# 04-USB2_Hub_BoardControlPeripherals.net
KiCad netlist of a schematic drawn in Altium Designer
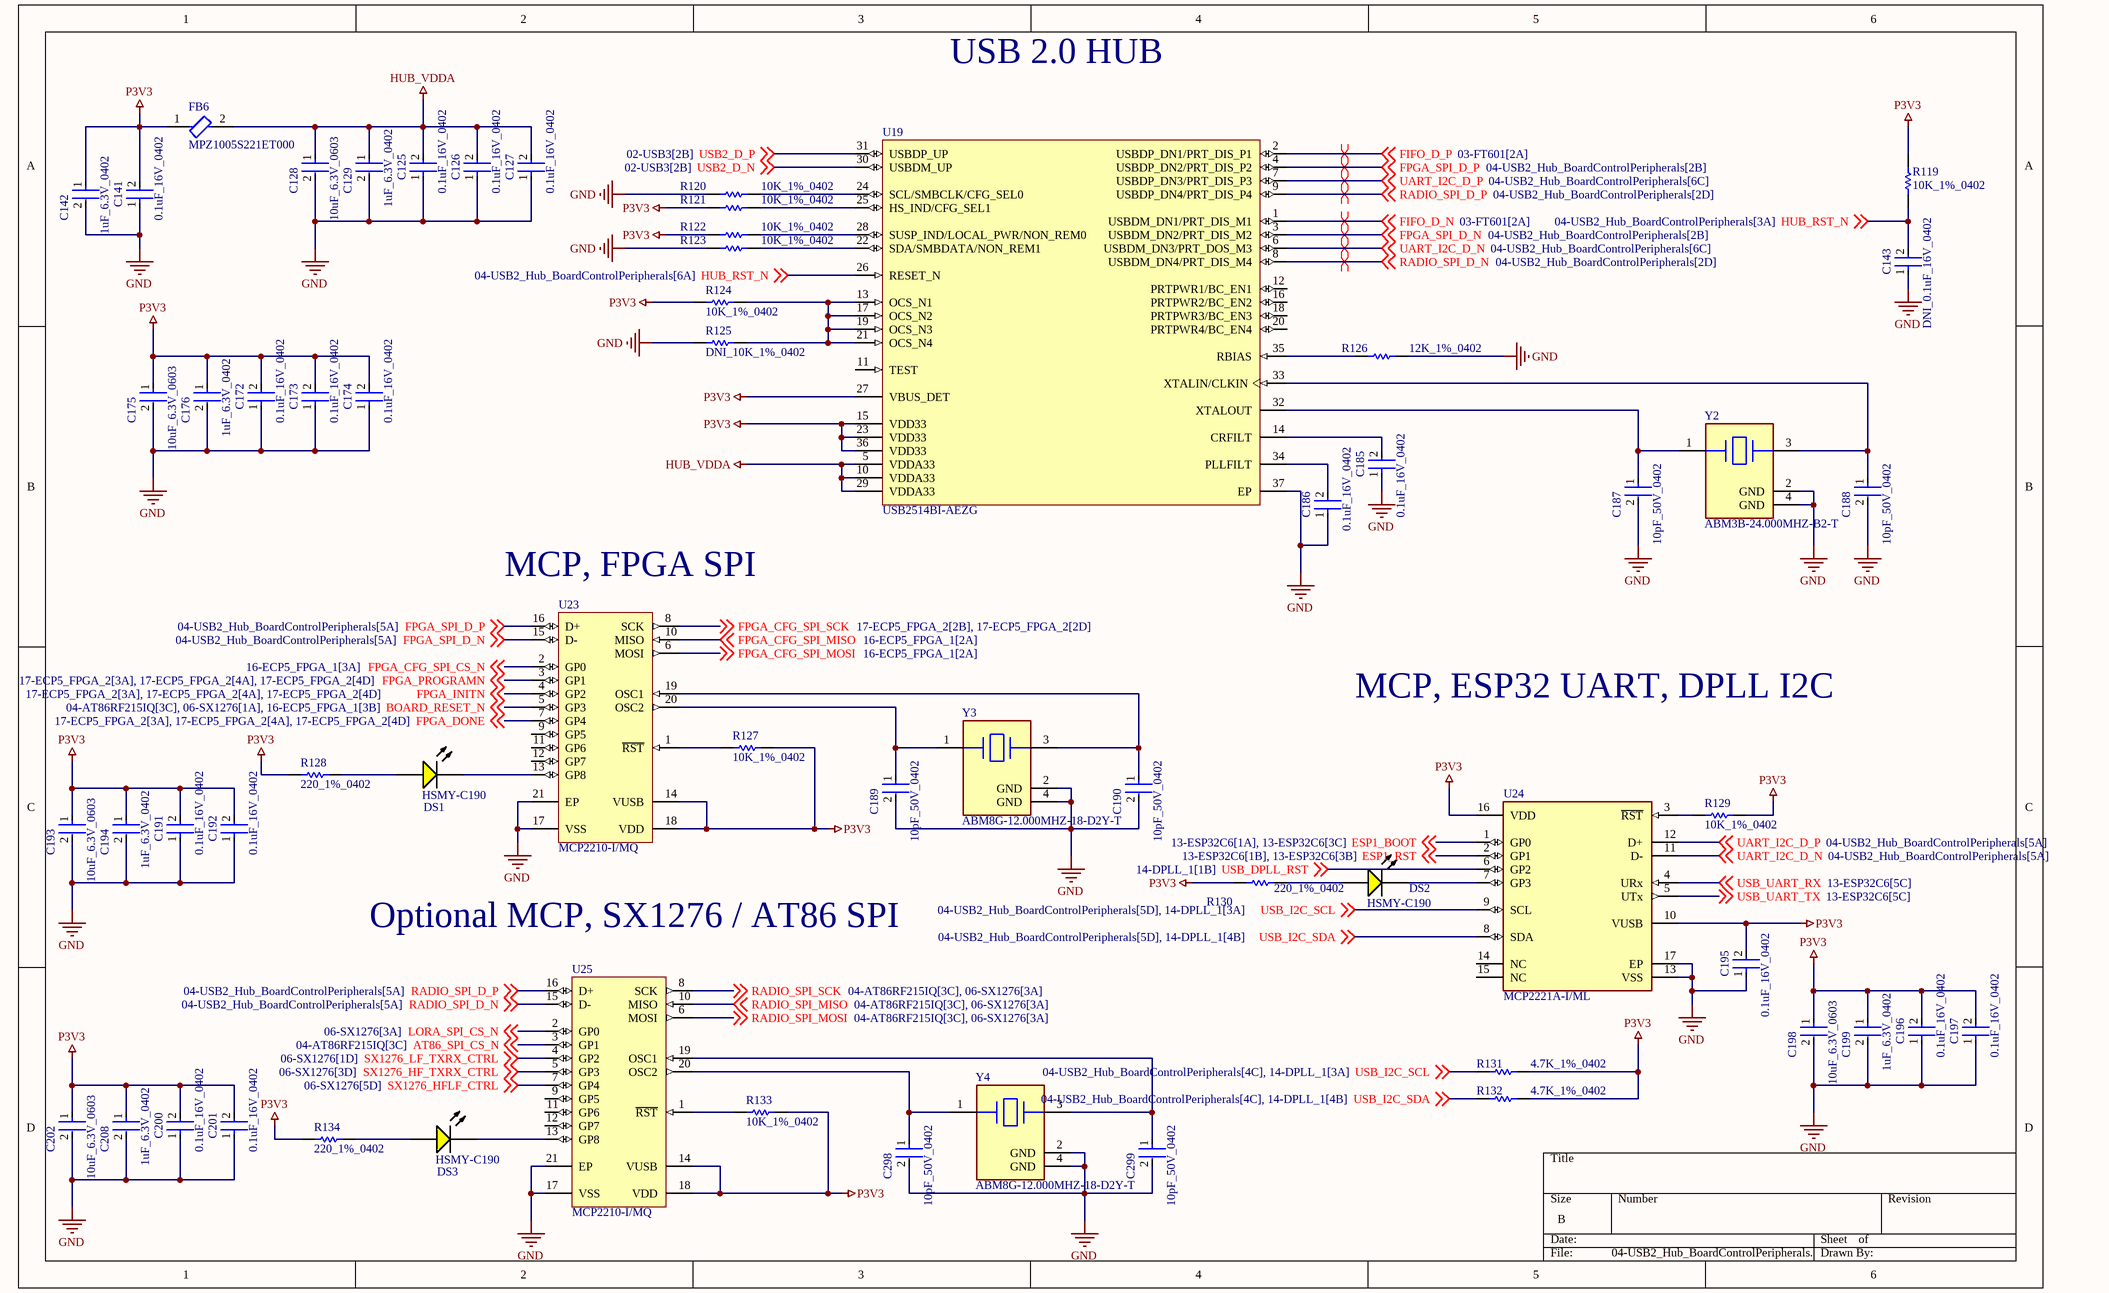
[diagram p0: 04-USB2_Hub_BoardControlPeripherals.SchDoc]

(export (version "E")
  (design (tool "Eeschema 10.0.6"))
  (components
    (comp (ref "C125")
      (value "0.1uF_16V_0402")
      (footprint "FP-C0402-BB-MFG")
      (description "CAP CER 0.1UF 16V 5% X7R 0402")
      (fields
        (field (name "MANUFACTURER") "Kemet")
        (field (name "MANUFACTURER PART NUMBER") "C0402C104J4RACTU")
      )
      (libsource (lib "Altium Content Vault") (part "b4654b650e69147ec39a6b967a45e02"))
    )
    (comp (ref "C126")
      (value "0.1uF_16V_0402")
      (footprint "FP-C0402-BB-MFG")
      (description "CAP CER 0.1UF 16V 5% X7R 0402")
      (fields
        (field (name "MANUFACTURER") "Kemet")
        (field (name "MANUFACTURER PART NUMBER") "C0402C104J4RACTU")
      )
      (libsource (lib "Altium Content Vault") (part "b4654b650e69147ec39a6b967a45e02"))
    )
    (comp (ref "C127")
      (value "0.1uF_16V_0402")
      (footprint "FP-C0402-BB-MFG")
      (description "CAP CER 0.1UF 16V 5% X7R 0402")
      (fields
        (field (name "MANUFACTURER") "Kemet")
        (field (name "MANUFACTURER PART NUMBER") "C0402C104J4RACTU")
      )
      (libsource (lib "Altium Content Vault") (part "b4654b650e69147ec39a6b967a45e02"))
    )
    (comp (ref "C128")
      (value "10uF_6.3V_0603")
      (footprint "FP-GRM188-0_1-e0_2_0_55-IPC_A")
      (description "Chip Multilayer Ceramic Capacitors for General Purpose, 0603, 10uF, X5R, 15%, 20%, 6.3V")
      (fields (field (name "VOLTAGE") "6.3V") (field (name "TOLERANCE") "20%"))
      (libsource (lib "Altium Content Vault") (part "02cd4be3c70576c341d710602a673aa"))
    )
    (comp (ref "C129")
      (value "1uF_6.3V_0402")
      (footprint "FP-CC0402-MFG")
      (description "CAP CER 1UF 6.3V X5R 0402")
      (fields
        (field (name "MANUFACTURER") "YAGEO")
        (field (name "OCTOPART") "https://octopart.com/cc0402krx5r5bb105-yageo-42244618")
      )
      (libsource (lib "Altium Content Vault") (part "11868f565c42a9108669ba33697ecf6"))
    )
    (comp (ref "C141")
      (value "0.1uF_16V_0402")
      (footprint "FP-C0402-BB-MFG")
      (description "CAP CER 0.1UF 16V 5% X7R 0402")
      (fields
        (field (name "MANUFACTURER") "Kemet")
        (field (name "MANUFACTURER PART NUMBER") "C0402C104J4RACTU")
      )
      (libsource (lib "Altium Content Vault") (part "b4654b650e69147ec39a6b967a45e02"))
    )
    (comp (ref "C142")
      (value "1uF_6.3V_0402")
      (footprint "FP-CC0402-MFG")
      (description "CAP CER 1UF 6.3V X5R 0402")
      (fields
        (field (name "MANUFACTURER") "YAGEO")
        (field (name "OCTOPART") "https://octopart.com/cc0402krx5r5bb105-yageo-42244618")
      )
      (libsource (lib "Altium Content Vault") (part "11868f565c42a9108669ba33697ecf6"))
    )
    (comp (ref "C143")
      (value "DNI_0.1uF_16V_0402")
      (footprint "FP-C0402-BB-MFG")
      (description "CAP CER 0.1UF 16V 5% X7R 0402")
      (fields
        (field (name "MANUFACTURER") "Kemet")
        (field (name "MANUFACTURER PART NUMBER") "C0402C104J4RACTU")
      )
      (libsource (lib "Altium Content Vault") (part "b4654b650e69147ec39a6b967a45e02"))
    )
    (comp (ref "C172")
      (value "0.1uF_16V_0402")
      (footprint "FP-C0402-BB-MFG")
      (description "CAP CER 0.1UF 16V 5% X7R 0402")
      (fields
        (field (name "MANUFACTURER") "Kemet")
        (field (name "MANUFACTURER PART NUMBER") "C0402C104J4RACTU")
      )
      (libsource (lib "Altium Content Vault") (part "b4654b650e69147ec39a6b967a45e02"))
    )
    (comp (ref "C173")
      (value "0.1uF_16V_0402")
      (footprint "FP-C0402-BB-MFG")
      (description "CAP CER 0.1UF 16V 5% X7R 0402")
      (fields
        (field (name "MANUFACTURER") "Kemet")
        (field (name "MANUFACTURER PART NUMBER") "C0402C104J4RACTU")
      )
      (libsource (lib "Altium Content Vault") (part "b4654b650e69147ec39a6b967a45e02"))
    )
    (comp (ref "C174")
      (value "0.1uF_16V_0402")
      (footprint "FP-C0402-BB-MFG")
      (description "CAP CER 0.1UF 16V 5% X7R 0402")
      (fields
        (field (name "MANUFACTURER") "Kemet")
        (field (name "MANUFACTURER PART NUMBER") "C0402C104J4RACTU")
      )
      (libsource (lib "Altium Content Vault") (part "b4654b650e69147ec39a6b967a45e02"))
    )
    (comp (ref "C175")
      (value "10uF_6.3V_0603")
      (footprint "FP-GRM188-0_1-e0_2_0_55-IPC_A")
      (description "Chip Multilayer Ceramic Capacitors for General Purpose, 0603, 10uF, X5R, 15%, 20%, 6.3V")
      (fields (field (name "VOLTAGE") "6.3V") (field (name "TOLERANCE") "20%"))
      (libsource (lib "Altium Content Vault") (part "02cd4be3c70576c341d710602a673aa"))
    )
    (comp (ref "C176")
      (value "1uF_6.3V_0402")
      (footprint "FP-CC0402-MFG")
      (description "CAP CER 1UF 6.3V X5R 0402")
      (fields
        (field (name "MANUFACTURER") "YAGEO")
        (field (name "OCTOPART") "https://octopart.com/cc0402krx5r5bb105-yageo-42244618")
      )
      (libsource (lib "Altium Content Vault") (part "11868f565c42a9108669ba33697ecf6"))
    )
    (comp (ref "C185")
      (value "0.1uF_16V_0402")
      (footprint "FP-C0402-BB-MFG")
      (description "CAP CER 0.1UF 16V 5% X7R 0402")
      (fields
        (field (name "MANUFACTURER") "Kemet")
        (field (name "MANUFACTURER PART NUMBER") "C0402C104J4RACTU")
      )
      (libsource (lib "Altium Content Vault") (part "b4654b650e69147ec39a6b967a45e02"))
    )
    (comp (ref "C186")
      (value "0.1uF_16V_0402")
      (footprint "FP-C0402-BB-MFG")
      (description "CAP CER 0.1UF 16V 5% X7R 0402")
      (fields
        (field (name "MANUFACTURER") "Kemet")
        (field (name "MANUFACTURER PART NUMBER") "C0402C104J4RACTU")
      )
      (libsource (lib "Altium Content Vault") (part "b4654b650e69147ec39a6b967a45e02"))
    )
    (comp (ref "C187")
      (value "10pF_50V_0402")
      (footprint "FP-C0402-BB-MFG")
      (fields
        (field (name "MANUFACTURER PART NUMBER") "C0402C100J5GACTU")
        (field (name "MANUFACTURER") "Kemet")
        (field (name "OCTOPART") "https://octopart.com/c0402c100j5gactu-kemet-108448")
      )
      (libsource (lib "Altium Content Vault") (part "b4654b650e69147ec39a6b967a45e02"))
    )
    (comp (ref "C188")
      (value "10pF_50V_0402")
      (footprint "FP-C0402-BB-MFG")
      (fields
        (field (name "MANUFACTURER PART NUMBER") "C0402C100J5GACTU")
        (field (name "MANUFACTURER") "Kemet")
        (field (name "OCTOPART") "https://octopart.com/c0402c100j5gactu-kemet-108448")
      )
      (libsource (lib "Altium Content Vault") (part "b4654b650e69147ec39a6b967a45e02"))
    )
    (comp (ref "C189")
      (value "10pF_50V_0402")
      (footprint "FP-C0402-BB-MFG")
      (fields
        (field (name "MANUFACTURER PART NUMBER") "C0402C100J5GACTU")
        (field (name "MANUFACTURER") "Kemet")
        (field (name "OCTOPART") "https://octopart.com/c0402c100j5gactu-kemet-108448")
      )
      (libsource (lib "Altium Content Vault") (part "b4654b650e69147ec39a6b967a45e02"))
    )
    (comp (ref "C190")
      (value "10pF_50V_0402")
      (footprint "FP-C0402-BB-MFG")
      (fields
        (field (name "MANUFACTURER PART NUMBER") "C0402C100J5GACTU")
        (field (name "MANUFACTURER") "Kemet")
        (field (name "OCTOPART") "https://octopart.com/c0402c100j5gactu-kemet-108448")
      )
      (libsource (lib "Altium Content Vault") (part "b4654b650e69147ec39a6b967a45e02"))
    )
    (comp (ref "C191")
      (value "0.1uF_16V_0402")
      (footprint "FP-C0402-BB-MFG")
      (description "CAP CER 0.1UF 16V 5% X7R 0402")
      (fields
        (field (name "MANUFACTURER") "Kemet")
        (field (name "MANUFACTURER PART NUMBER") "C0402C104J4RACTU")
      )
      (libsource (lib "Altium Content Vault") (part "b4654b650e69147ec39a6b967a45e02"))
    )
    (comp (ref "C192")
      (value "0.1uF_16V_0402")
      (footprint "FP-C0402-BB-MFG")
      (description "CAP CER 0.1UF 16V 5% X7R 0402")
      (fields
        (field (name "MANUFACTURER") "Kemet")
        (field (name "MANUFACTURER PART NUMBER") "C0402C104J4RACTU")
      )
      (libsource (lib "Altium Content Vault") (part "b4654b650e69147ec39a6b967a45e02"))
    )
    (comp (ref "C193")
      (value "10uF_6.3V_0603")
      (footprint "FP-GRM188-0_1-e0_2_0_55-IPC_A")
      (description "Chip Multilayer Ceramic Capacitors for General Purpose, 0603, 10uF, X5R, 15%, 20%, 6.3V")
      (fields (field (name "VOLTAGE") "6.3V") (field (name "TOLERANCE") "20%"))
      (libsource (lib "Altium Content Vault") (part "02cd4be3c70576c341d710602a673aa"))
    )
    (comp (ref "C194")
      (value "1uF_6.3V_0402")
      (footprint "FP-CC0402-MFG")
      (description "CAP CER 1UF 6.3V X5R 0402")
      (fields
        (field (name "MANUFACTURER") "YAGEO")
        (field (name "OCTOPART") "https://octopart.com/cc0402krx5r5bb105-yageo-42244618")
      )
      (libsource (lib "Altium Content Vault") (part "11868f565c42a9108669ba33697ecf6"))
    )
    (comp (ref "C195")
      (value "0.1uF_16V_0402")
      (footprint "FP-C0402-BB-MFG")
      (description "CAP CER 0.1UF 16V 5% X7R 0402")
      (fields
        (field (name "MANUFACTURER") "Kemet")
        (field (name "MANUFACTURER PART NUMBER") "C0402C104J4RACTU")
      )
      (libsource (lib "Altium Content Vault") (part "b4654b650e69147ec39a6b967a45e02"))
    )
    (comp (ref "C196")
      (value "0.1uF_16V_0402")
      (footprint "FP-C0402-BB-MFG")
      (description "CAP CER 0.1UF 16V 5% X7R 0402")
      (fields
        (field (name "MANUFACTURER") "Kemet")
        (field (name "MANUFACTURER PART NUMBER") "C0402C104J4RACTU")
      )
      (libsource (lib "Altium Content Vault") (part "b4654b650e69147ec39a6b967a45e02"))
    )
    (comp (ref "C197")
      (value "0.1uF_16V_0402")
      (footprint "FP-C0402-BB-MFG")
      (description "CAP CER 0.1UF 16V 5% X7R 0402")
      (fields
        (field (name "MANUFACTURER") "Kemet")
        (field (name "MANUFACTURER PART NUMBER") "C0402C104J4RACTU")
      )
      (libsource (lib "Altium Content Vault") (part "b4654b650e69147ec39a6b967a45e02"))
    )
    (comp (ref "C198")
      (value "10uF_6.3V_0603")
      (footprint "FP-GRM188-0_1-e0_2_0_55-IPC_A")
      (description "Chip Multilayer Ceramic Capacitors for General Purpose, 0603, 10uF, X5R, 15%, 20%, 6.3V")
      (fields (field (name "VOLTAGE") "6.3V") (field (name "TOLERANCE") "20%"))
      (libsource (lib "Altium Content Vault") (part "02cd4be3c70576c341d710602a673aa"))
    )
    (comp (ref "C199")
      (value "1uF_6.3V_0402")
      (footprint "FP-CC0402-MFG")
      (description "CAP CER 1UF 6.3V X5R 0402")
      (fields
        (field (name "MANUFACTURER") "YAGEO")
        (field (name "OCTOPART") "https://octopart.com/cc0402krx5r5bb105-yageo-42244618")
      )
      (libsource (lib "Altium Content Vault") (part "11868f565c42a9108669ba33697ecf6"))
    )
    (comp (ref "C200")
      (value "0.1uF_16V_0402")
      (footprint "FP-C0402-BB-MFG")
      (description "CAP CER 0.1UF 16V 5% X7R 0402")
      (fields
        (field (name "MANUFACTURER") "Kemet")
        (field (name "MANUFACTURER PART NUMBER") "C0402C104J4RACTU")
      )
      (libsource (lib "Altium Content Vault") (part "b4654b650e69147ec39a6b967a45e02"))
    )
    (comp (ref "C201")
      (value "0.1uF_16V_0402")
      (footprint "FP-C0402-BB-MFG")
      (description "CAP CER 0.1UF 16V 5% X7R 0402")
      (fields
        (field (name "MANUFACTURER") "Kemet")
        (field (name "MANUFACTURER PART NUMBER") "C0402C104J4RACTU")
      )
      (libsource (lib "Altium Content Vault") (part "b4654b650e69147ec39a6b967a45e02"))
    )
    (comp (ref "C202")
      (value "10uF_6.3V_0603")
      (footprint "FP-GRM188-0_1-e0_2_0_55-IPC_A")
      (description "Chip Multilayer Ceramic Capacitors for General Purpose, 0603, 10uF, X5R, 15%, 20%, 6.3V")
      (fields (field (name "VOLTAGE") "6.3V") (field (name "TOLERANCE") "20%"))
      (libsource (lib "Altium Content Vault") (part "02cd4be3c70576c341d710602a673aa"))
    )
    (comp (ref "C208")
      (value "1uF_6.3V_0402")
      (footprint "FP-CC0402-MFG")
      (description "CAP CER 1UF 6.3V X5R 0402")
      (fields
        (field (name "MANUFACTURER") "YAGEO")
        (field (name "OCTOPART") "https://octopart.com/cc0402krx5r5bb105-yageo-42244618")
      )
      (libsource (lib "Altium Content Vault") (part "11868f565c42a9108669ba33697ecf6"))
    )
    (comp (ref "C298")
      (value "10pF_50V_0402")
      (footprint "FP-C0402-BB-MFG")
      (fields
        (field (name "MANUFACTURER PART NUMBER") "C0402C100J5GACTU")
        (field (name "MANUFACTURER") "Kemet")
        (field (name "OCTOPART") "https://octopart.com/c0402c100j5gactu-kemet-108448")
      )
      (libsource (lib "Altium Content Vault") (part "b4654b650e69147ec39a6b967a45e02"))
    )
    (comp (ref "C299")
      (value "10pF_50V_0402")
      (footprint "FP-C0402-BB-MFG")
      (fields
        (field (name "MANUFACTURER PART NUMBER") "C0402C100J5GACTU")
        (field (name "MANUFACTURER") "Kemet")
        (field (name "OCTOPART") "https://octopart.com/c0402c100j5gactu-kemet-108448")
      )
      (libsource (lib "Altium Content Vault") (part "b4654b650e69147ec39a6b967a45e02"))
    )
    (comp (ref "DS1")
      (value "HSMY-C190")
      (footprint "AVAG-HSMX-C190_V")
      (description "LED Uni-Color Yellow, 65 mW, 20 mA, -40 to 85 degC, 2-Pin SMD, RoHS, Tape and Reel")
      (fields (field (name "TOLERANCE") "1%"))
      (libsource (lib "Altium Content Vault") (part "LED-YELLOW-AK-2"))
    )
    (comp (ref "DS2")
      (value "HSMY-C190")
      (footprint "AVAG-HSMX-C190_V")
      (description "LED Uni-Color Yellow, 65 mW, 20 mA, -40 to 85 degC, 2-Pin SMD, RoHS, Tape and Reel")
      (fields (field (name "TOLERANCE") "1%"))
      (libsource (lib "Altium Content Vault") (part "LED-YELLOW-AK-2"))
    )
    (comp (ref "DS3")
      (value "HSMY-C190")
      (footprint "AVAG-HSMX-C190_V")
      (description "LED Uni-Color Yellow, 65 mW, 20 mA, -40 to 85 degC, 2-Pin SMD, RoHS, Tape and Reel")
      (fields (field (name "TOLERANCE") "1%"))
      (libsource (lib "Altium Content Vault") (part "LED-YELLOW-AK-2"))
    )
    (comp (ref "FB6")
      (value "MPZ1005S221ET000")
      (footprint "FP-MPZ1005-IPC_A")
      (description "Power line Ferrite Bead 220Ω @ 100MHz 0.9A DCR 0.22Ω SMD 0402")
      (fields (field (name "TOLERANCE") "25%"))
      (libsource (lib "Altium Content Vault") (part "5f30dd21d616792df468990f7003faa"))
    )
    (comp (ref "R119")
      (value "10K_1%_0402")
      (footprint "RESC1005X40X25NL10T10")
      (fields (field (name "MANUFACTURER") "Bourns") (field (name "PART NUMBER") "CR0402-FX-1002GLF"))
      (libsource (lib "Altium Content Vault") (part "RES"))
    )
    (comp (ref "R120")
      (value "10K_1%_0402")
      (footprint "RESC1005X40X25NL10T10")
      (fields (field (name "MANUFACTURER") "Bourns") (field (name "PART NUMBER") "CR0402-FX-1002GLF"))
      (libsource (lib "Altium Content Vault") (part "RES"))
    )
    (comp (ref "R121")
      (value "10K_1%_0402")
      (footprint "RESC1005X40X25NL10T10")
      (fields (field (name "MANUFACTURER") "Bourns") (field (name "PART NUMBER") "CR0402-FX-1002GLF"))
      (libsource (lib "Altium Content Vault") (part "RES"))
    )
    (comp (ref "R122")
      (value "10K_1%_0402")
      (footprint "RESC1005X40X25NL10T10")
      (fields (field (name "MANUFACTURER") "Bourns") (field (name "PART NUMBER") "CR0402-FX-1002GLF"))
      (libsource (lib "Altium Content Vault") (part "RES"))
    )
    (comp (ref "R123")
      (value "10K_1%_0402")
      (footprint "RESC1005X40X25NL10T10")
      (fields (field (name "MANUFACTURER") "Bourns") (field (name "PART NUMBER") "CR0402-FX-1002GLF"))
      (libsource (lib "Altium Content Vault") (part "RES"))
    )
    (comp (ref "R124")
      (value "10K_1%_0402")
      (footprint "RESC1005X40X25NL10T10")
      (fields (field (name "MANUFACTURER") "Bourns") (field (name "PART NUMBER") "CR0402-FX-1002GLF"))
      (libsource (lib "Altium Content Vault") (part "RES"))
    )
    (comp (ref "R125")
      (value "DNI_10K_1%_0402")
      (footprint "RESC1005X40X25NL10T10")
      (fields (field (name "MANUFACTURER") "Bourns") (field (name "PART NUMBER") "CR0402-FX-1002GLF"))
      (libsource (lib "Altium Content Vault") (part "RES"))
    )
    (comp (ref "R126")
      (value "12K_1%_0402")
      (footprint "RESC1005X40X25LL10T10")
      (fields
        (field (name "PART NUMBER") "CRG0402F12K")
        (field (name "MANUFACTURER") "TE Connectivity / AMP")
      )
      (libsource (lib "Altium Content Vault") (part "RES"))
    )
    (comp (ref "R127")
      (value "10K_1%_0402")
      (footprint "RESC1005X40X25NL10T10")
      (fields (field (name "MANUFACTURER") "Bourns") (field (name "PART NUMBER") "CR0402-FX-1002GLF"))
      (libsource (lib "Altium Content Vault") (part "RES"))
    )
    (comp (ref "R128")
      (value "220_1%_0402")
      (footprint "RESC1005X40X25LL05T05")
      (fields (field (name "MANUFACTURER") "Panasonic") (field (name "PART NUMBER") "ERJ2RKF2200X"))
      (libsource (lib "Altium Content Vault") (part "RES"))
    )
    (comp (ref "R129")
      (value "10K_1%_0402")
      (footprint "RESC1005X40X25NL10T10")
      (fields (field (name "MANUFACTURER") "Bourns") (field (name "PART NUMBER") "CR0402-FX-1002GLF"))
      (libsource (lib "Altium Content Vault") (part "RES"))
    )
    (comp (ref "R130")
      (value "220_1%_0402")
      (footprint "RESC1005X40X25LL05T05")
      (fields (field (name "MANUFACTURER") "Panasonic") (field (name "PART NUMBER") "ERJ2RKF2200X"))
      (libsource (lib "Altium Content Vault") (part "RES"))
    )
    (comp (ref "R131")
      (value "4.7K_1%_0402")
      (footprint "RESC1005X40X25NL05T10")
      (fields (field (name "MANUFACTURER") "Yageo / Phycomp") (field (name "PART NUMBER") "RC0402FR-074K7L"))
      (libsource (lib "Altium Content Vault") (part "RES"))
    )
    (comp (ref "R132")
      (value "4.7K_1%_0402")
      (footprint "RESC1005X40X25NL05T10")
      (fields (field (name "MANUFACTURER") "Yageo / Phycomp") (field (name "PART NUMBER") "RC0402FR-074K7L"))
      (libsource (lib "Altium Content Vault") (part "RES"))
    )
    (comp (ref "R133")
      (value "10K_1%_0402")
      (footprint "RESC1005X40X25NL10T10")
      (fields (field (name "MANUFACTURER") "Bourns") (field (name "PART NUMBER") "CR0402-FX-1002GLF"))
      (libsource (lib "Altium Content Vault") (part "RES"))
    )
    (comp (ref "R134")
      (value "220_1%_0402")
      (footprint "RESC1005X40X25LL05T05")
      (fields (field (name "MANUFACTURER") "Panasonic") (field (name "PART NUMBER") "ERJ2RKF2200X"))
      (libsource (lib "Altium Content Vault") (part "RES"))
    )
    (comp (ref "U19")
      (value "USB2514BI-AEZG")
      (footprint "MCHP-QFN-36_V")
      (description "USB 2.0 Hi-Speed Hub Controller, 3 to 3.6 V, -40 to 85 degC, 36-Pin QFN, RoHS, Tape and Reel")
      (fields (field (name "MANUFACTURER") "Microchip"))
      (libsource (lib "Altium Content Vault") (part "MCHP-USB2514-QFN-36"))
    )
    (comp (ref "U23")
      (value "MCP2210-I/MQ")
      (footprint "QFN-MQ20_L")
      (description "USB-to-SPI Protocol Converter with GPIO (Master Mode), 20-Pin QFN, Industrial Temperature")
      (libsource (lib "Altium Content Vault") (part "COM-USB-MCP2210-21"))
    )
    (comp (ref "U24")
      (value "MCP2221A-I/ML")
      (footprint "FP-C04-127-MFG")
      (description "IC USB TO I2C/UART 16QFN")
      (libsource (lib "Altium Content Vault") (part "9a58687fb20c11cd38d39b7dac8df0f"))
    )
    (comp (ref "U25")
      (value "MCP2210-I/MQ")
      (footprint "QFN-MQ20_L")
      (description "USB-to-SPI Protocol Converter with GPIO (Master Mode), 20-Pin QFN, Industrial Temperature")
      (libsource (lib "Altium Content Vault") (part "COM-USB-MCP2210-21"))
    )
    (comp (ref "Y2")
      (value "ABM3B-24.000MHZ-B2-T")
      (footprint "FP-ABM3B-MFG")
      (description "Crystal 24MHz ±20ppm 18pF SMD-4 5mm x 3.2mm")
      (fields (field (name "TOLERANCE") "20ppm"))
      (libsource (lib "Altium Content Vault") (part "48e526d86b7f2615d98721063c72f49"))
    )
    (comp (ref "Y3")
      (value "ABM8G-12.000MHZ-18-D2Y-T")
      (footprint "FP-ABM8G-MFG")
      (description "Crystal 12MHz ±20ppm (Tol) ±30ppm (Stability) 18pF FUND 120Ω 4-Pin SMD T/R")
      (fields (field (name "TOLERANCE") "20ppm"))
      (libsource (lib "Altium Content Vault") (part "48e526d86b7f2615d98721063c72f49"))
    )
    (comp (ref "Y4")
      (value "ABM8G-12.000MHZ-18-D2Y-T")
      (footprint "FP-ABM8G-MFG")
      (description "Crystal 12MHz ±20ppm (Tol) ±30ppm (Stability) 18pF FUND 120Ω 4-Pin SMD T/R")
      (fields (field (name "TOLERANCE") "20ppm"))
      (libsource (lib "Altium Content Vault") (part "48e526d86b7f2615d98721063c72f49"))
    )
  )
  (nets
    (net (code "1") (name "AT86_SPI_CS_N") (class "Default")
      (node (ref "U25") (pin "3") (pinfunction "GP1_3") (pintype "bidirectional"))
    )
    (net (code "2") (name "BOARD_RESET_N") (class "Default")
      (node (ref "U23") (pin "5") (pinfunction "GP3_5") (pintype "bidirectional"))
    )
    (net (code "3") (name "ESP1_BOOT") (class "Default")
      (node (ref "U24") (pin "1") (pinfunction "GP0_1") (pintype "bidirectional"))
    )
    (net (code "4") (name "ESP1_RST") (class "Default")
      (node (ref "U24") (pin "2") (pinfunction "GP1_2") (pintype "bidirectional"))
    )
    (net (code "5") (name "FIFO_D_N") (class "Default")
      (node (ref "U19") (pin "1") (pinfunction "USBDM_DN1/PRT_DIS_M1_1") (pintype "bidirectional"))
    )
    (net (code "6") (name "FIFO_D_P") (class "Default")
      (node (ref "U19") (pin "2") (pinfunction "USBDP_DN1/PRT_DIS_P1_2") (pintype "bidirectional"))
    )
    (net (code "7") (name "FPGA_CFG_SPI_CS_N") (class "Default")
      (node (ref "U23") (pin "2") (pinfunction "GP0_2") (pintype "bidirectional"))
    )
    (net (code "8") (name "FPGA_CFG_SPI_MISO") (class "Default")
      (node (ref "U23") (pin "10") (pinfunction "MISO_10") (pintype "input"))
    )
    (net (code "9") (name "FPGA_CFG_SPI_MOSI") (class "Default")
      (node (ref "U23") (pin "6") (pinfunction "MOSI_6") (pintype "output"))
    )
    (net (code "10") (name "FPGA_CFG_SPI_SCK") (class "Default")
      (node (ref "U23") (pin "8") (pinfunction "SCK_8") (pintype "output"))
    )
    (net (code "11") (name "FPGA_DONE") (class "Default")
      (node (ref "U23") (pin "7") (pinfunction "GP4_7") (pintype "bidirectional"))
    )
    (net (code "12") (name "FPGA_INITN") (class "Default")
      (node (ref "U23") (pin "4") (pinfunction "GP2_4") (pintype "bidirectional"))
    )
    (net (code "13") (name "FPGA_PROGRAMN") (class "Default")
      (node (ref "U23") (pin "3") (pinfunction "GP1_3") (pintype "bidirectional"))
    )
    (net (code "14") (name "FPGA_SPI_D_N") (class "Default")
      (node (ref "U19") (pin "3") (pinfunction "USBDM_DN2/PRT_DIS_M2_3") (pintype "bidirectional"))
      (node (ref "U23") (pin "15") (pinfunction "D-_15") (pintype "bidirectional"))
    )
    (net (code "15") (name "FPGA_SPI_D_P") (class "Default")
      (node (ref "U19") (pin "4") (pinfunction "USBDP_DN2/PRT_DIS_P2_4") (pintype "bidirectional"))
      (node (ref "U23") (pin "16") (pinfunction "D+_16") (pintype "bidirectional"))
    )
    (net (code "16") (name "GND") (class "Default")
      (node (ref "C125") (pin "1") (pinfunction "1_1") (pintype "passive"))
      (node (ref "C126") (pin "1") (pinfunction "1_1") (pintype "passive"))
      (node (ref "C127") (pin "1") (pinfunction "1_1") (pintype "passive"))
      (node (ref "C128") (pin "2") (pinfunction "2_2") (pintype "passive"))
      (node (ref "C129") (pin "2") (pinfunction "2_2") (pintype "passive"))
      (node (ref "C141") (pin "1") (pinfunction "1_1") (pintype "passive"))
      (node (ref "C142") (pin "2") (pinfunction "2_2") (pintype "passive"))
      (node (ref "C143") (pin "1") (pinfunction "1_1") (pintype "passive"))
      (node (ref "C172") (pin "1") (pinfunction "1_1") (pintype "passive"))
      (node (ref "C173") (pin "1") (pinfunction "1_1") (pintype "passive"))
      (node (ref "C174") (pin "1") (pinfunction "1_1") (pintype "passive"))
      (node (ref "C175") (pin "2") (pinfunction "2_2") (pintype "passive"))
      (node (ref "C176") (pin "2") (pinfunction "2_2") (pintype "passive"))
      (node (ref "C185") (pin "1") (pinfunction "1_1") (pintype "passive"))
      (node (ref "C186") (pin "1") (pinfunction "1_1") (pintype "passive"))
      (node (ref "C187") (pin "2") (pinfunction "2_2") (pintype "passive"))
      (node (ref "C188") (pin "2") (pinfunction "2_2") (pintype "passive"))
      (node (ref "C189") (pin "2") (pinfunction "2_2") (pintype "passive"))
      (node (ref "C190") (pin "2") (pinfunction "2_2") (pintype "passive"))
      (node (ref "C191") (pin "1") (pinfunction "1_1") (pintype "passive"))
      (node (ref "C192") (pin "1") (pinfunction "1_1") (pintype "passive"))
      (node (ref "C193") (pin "2") (pinfunction "2_2") (pintype "passive"))
      (node (ref "C194") (pin "2") (pinfunction "2_2") (pintype "passive"))
      (node (ref "C195") (pin "1") (pinfunction "1_1") (pintype "passive"))
      (node (ref "C196") (pin "1") (pinfunction "1_1") (pintype "passive"))
      (node (ref "C197") (pin "1") (pinfunction "1_1") (pintype "passive"))
      (node (ref "C198") (pin "2") (pinfunction "2_2") (pintype "passive"))
      (node (ref "C199") (pin "2") (pinfunction "2_2") (pintype "passive"))
      (node (ref "C200") (pin "1") (pinfunction "1_1") (pintype "passive"))
      (node (ref "C201") (pin "1") (pinfunction "1_1") (pintype "passive"))
      (node (ref "C202") (pin "2") (pinfunction "2_2") (pintype "passive"))
      (node (ref "C208") (pin "2") (pinfunction "2_2") (pintype "passive"))
      (node (ref "C298") (pin "2") (pinfunction "2_2") (pintype "passive"))
      (node (ref "C299") (pin "2") (pinfunction "2_2") (pintype "passive"))
      (node (ref "R120") (pin "1") (pinfunction "1_1") (pintype "passive"))
      (node (ref "R123") (pin "1") (pinfunction "1_1") (pintype "passive"))
      (node (ref "R125") (pin "1") (pinfunction "1_1") (pintype "passive"))
      (node (ref "R126") (pin "2") (pinfunction "2_2") (pintype "passive"))
      (node (ref "U19") (pin "37") (pinfunction "EP_37") (pintype "power_in"))
      (node (ref "U23") (pin "17") (pinfunction "VSS_17") (pintype "power_in"))
      (node (ref "U23") (pin "21") (pinfunction "EP_21") (pintype "passive"))
      (node (ref "U24") (pin "13") (pinfunction "VSS_13") (pintype "power_in"))
      (node (ref "U24") (pin "17") (pinfunction "EP_17") (pintype "power_in"))
      (node (ref "U25") (pin "17") (pinfunction "VSS_17") (pintype "power_in"))
      (node (ref "U25") (pin "21") (pinfunction "EP_21") (pintype "passive"))
      (node (ref "Y2") (pin "2") (pinfunction "GND_2") (pintype "power_in"))
      (node (ref "Y2") (pin "4") (pinfunction "GND_4") (pintype "power_in"))
      (node (ref "Y3") (pin "2") (pinfunction "GND_2") (pintype "power_in"))
      (node (ref "Y3") (pin "4") (pinfunction "GND_4") (pintype "power_in"))
      (node (ref "Y4") (pin "2") (pinfunction "GND_2") (pintype "power_in"))
      (node (ref "Y4") (pin "4") (pinfunction "GND_4") (pintype "power_in"))
    )
    (net (code "17") (name "HUB_RST_N") (class "Default")
      (node (ref "C143") (pin "2") (pinfunction "2_2") (pintype "passive"))
      (node (ref "R119") (pin "1") (pinfunction "1_1") (pintype "passive"))
      (node (ref "U19") (pin "26") (pinfunction "RESET_N_26") (pintype "input"))
    )
    (net (code "18") (name "HUB_VDDA") (class "Default")
      (node (ref "C125") (pin "2") (pinfunction "2_2") (pintype "passive"))
      (node (ref "C126") (pin "2") (pinfunction "2_2") (pintype "passive"))
      (node (ref "C127") (pin "2") (pinfunction "2_2") (pintype "passive"))
      (node (ref "C128") (pin "1") (pinfunction "1_1") (pintype "passive"))
      (node (ref "C129") (pin "1") (pinfunction "1_1") (pintype "passive"))
      (node (ref "FB6") (pin "2") (pinfunction "2_2") (pintype "passive"))
      (node (ref "U19") (pin "10") (pinfunction "VDDA33_10") (pintype "power_in"))
      (node (ref "U19") (pin "29") (pinfunction "VDDA33_29") (pintype "power_in"))
      (node (ref "U19") (pin "5") (pinfunction "VDDA33_5") (pintype "power_in"))
    )
    (net (code "19") (name "LORA_SPI_CS_N") (class "Default")
      (node (ref "U25") (pin "2") (pinfunction "GP0_2") (pintype "bidirectional"))
    )
    (net (code "20") (name "Net-(DS1-A)") (class "Default")
      (node (ref "DS1") (pin "1") (pinfunction "A_1") (pintype "passive"))
      (node (ref "R128") (pin "2") (pinfunction "2_2") (pintype "passive"))
    )
    (net (code "21") (name "Net-(DS1-K)") (class "Default")
      (node (ref "DS1") (pin "2") (pinfunction "K_2") (pintype "passive"))
      (node (ref "U23") (pin "13") (pinfunction "GP8_13") (pintype "bidirectional"))
    )
    (net (code "22") (name "Net-(DS2-A)") (class "Default")
      (node (ref "DS2") (pin "1") (pinfunction "A_1") (pintype "passive"))
      (node (ref "R130") (pin "2") (pinfunction "2_2") (pintype "passive"))
    )
    (net (code "23") (name "Net-(DS2-K)") (class "Default")
      (node (ref "DS2") (pin "2") (pinfunction "K_2") (pintype "passive"))
      (node (ref "U24") (pin "7") (pinfunction "GP3_7") (pintype "bidirectional"))
    )
    (net (code "24") (name "Net-(DS3-A)") (class "Default")
      (node (ref "DS3") (pin "1") (pinfunction "A_1") (pintype "passive"))
      (node (ref "R134") (pin "2") (pinfunction "2_2") (pintype "passive"))
    )
    (net (code "25") (name "Net-(DS3-K)") (class "Default")
      (node (ref "DS3") (pin "2") (pinfunction "K_2") (pintype "passive"))
      (node (ref "U25") (pin "13") (pinfunction "GP8_13") (pintype "bidirectional"))
    )
    (net (code "26") (name "Net-(U19-CRFILT)") (class "Default")
      (node (ref "C185") (pin "2") (pinfunction "2_2") (pintype "passive"))
      (node (ref "U19") (pin "14") (pinfunction "CRFILT_14") (pintype "passive"))
    )
    (net (code "27") (name "Net-(U19-HS_IND{slash}CFG_SEL1)") (class "Default")
      (node (ref "R121") (pin "2") (pinfunction "2_2") (pintype "passive"))
      (node (ref "U19") (pin "25") (pinfunction "HS_IND/CFG_SEL1_25") (pintype "bidirectional"))
    )
    (net (code "28") (name "Net-(U19-OCS_N1)") (class "Default")
      (node (ref "R124") (pin "2") (pinfunction "2_2") (pintype "passive"))
      (node (ref "R125") (pin "2") (pinfunction "2_2") (pintype "passive"))
      (node (ref "U19") (pin "13") (pinfunction "OCS_N1_13") (pintype "input"))
      (node (ref "U19") (pin "17") (pinfunction "OCS_N2_17") (pintype "input"))
      (node (ref "U19") (pin "19") (pinfunction "OCS_N3_19") (pintype "input"))
      (node (ref "U19") (pin "21") (pinfunction "OCS_N4_21") (pintype "input"))
    )
    (net (code "29") (name "Net-(U19-PLLFILT)") (class "Default")
      (node (ref "C186") (pin "2") (pinfunction "2_2") (pintype "passive"))
      (node (ref "U19") (pin "34") (pinfunction "PLLFILT_34") (pintype "passive"))
    )
    (net (code "30") (name "Net-(U19-RBIAS)") (class "Default")
      (node (ref "R126") (pin "1") (pinfunction "1_1") (pintype "passive"))
      (node (ref "U19") (pin "35") (pinfunction "RBIAS_35") (pintype "input"))
    )
    (net (code "31") (name "Net-(U19-SCL{slash}SMBCLK{slash}CFG_SEL0)") (class "Default")
      (node (ref "R120") (pin "2") (pinfunction "2_2") (pintype "passive"))
      (node (ref "U19") (pin "24") (pinfunction "SCL/SMBCLK/CFG_SEL0_24") (pintype "bidirectional"))
    )
    (net (code "32") (name "Net-(U19-SDA{slash}SMBDATA{slash}NON_REM1)") (class "Default")
      (node (ref "R123") (pin "2") (pinfunction "2_2") (pintype "passive"))
      (node (ref "U19") (pin "22") (pinfunction "SDA/SMBDATA/NON_REM1_22") (pintype "bidirectional"))
    )
    (net (code "33") (name "Net-(U19-SUSP_IND{slash}LOCAL_PWR{slash}NON_REM0)") (class "Default")
      (node (ref "R122") (pin "2") (pinfunction "2_2") (pintype "passive"))
      (node (ref "U19") (pin "28") (pinfunction "SUSP_IND/LOCAL_PWR/NON_REM0_28") (pintype "bidirectional"))
    )
    (net (code "34") (name "Net-(U19-XTALIN{slash}CLKIN)") (class "Default")
      (node (ref "C188") (pin "1") (pinfunction "1_1") (pintype "passive"))
      (node (ref "U19") (pin "33") (pinfunction "XTALIN/CLKIN_33") (pintype "input"))
      (node (ref "Y2") (pin "3") (pinfunction "3_3") (pintype "passive"))
    )
    (net (code "35") (name "Net-(U19-XTALOUT)") (class "Default")
      (node (ref "C187") (pin "1") (pinfunction "1_1") (pintype "passive"))
      (node (ref "U19") (pin "32") (pinfunction "XTALOUT_32") (pintype "passive"))
      (node (ref "Y2") (pin "1") (pinfunction "1_1") (pintype "passive"))
    )
    (net (code "36") (name "Net-(U23-OSC1)") (class "Default")
      (node (ref "C190") (pin "1") (pinfunction "1_1") (pintype "passive"))
      (node (ref "U23") (pin "19") (pinfunction "OSC1_19") (pintype "input"))
      (node (ref "Y3") (pin "3") (pinfunction "3_3") (pintype "passive"))
    )
    (net (code "37") (name "Net-(U23-OSC2)") (class "Default")
      (node (ref "C189") (pin "1") (pinfunction "1_1") (pintype "passive"))
      (node (ref "U23") (pin "20") (pinfunction "OSC2_20") (pintype "output"))
      (node (ref "Y3") (pin "1") (pinfunction "1_1") (pintype "passive"))
    )
    (net (code "38") (name "Net-(U23-~{RST})") (class "Default")
      (node (ref "R127") (pin "1") (pinfunction "1_1") (pintype "passive"))
      (node (ref "U23") (pin "1") (pinfunction "~{RST}_1") (pintype "input"))
    )
    (net (code "39") (name "Net-(U24-~{RST})") (class "Default")
      (node (ref "R129") (pin "1") (pinfunction "1_1") (pintype "passive"))
      (node (ref "U24") (pin "3") (pinfunction "~{RST}_3") (pintype "input"))
    )
    (net (code "40") (name "Net-(U25-OSC1)") (class "Default")
      (node (ref "C299") (pin "1") (pinfunction "1_1") (pintype "passive"))
      (node (ref "U25") (pin "19") (pinfunction "OSC1_19") (pintype "input"))
      (node (ref "Y4") (pin "3") (pinfunction "3_3") (pintype "passive"))
    )
    (net (code "41") (name "Net-(U25-OSC2)") (class "Default")
      (node (ref "C298") (pin "1") (pinfunction "1_1") (pintype "passive"))
      (node (ref "U25") (pin "20") (pinfunction "OSC2_20") (pintype "output"))
      (node (ref "Y4") (pin "1") (pinfunction "1_1") (pintype "passive"))
    )
    (net (code "42") (name "Net-(U25-~{RST})") (class "Default")
      (node (ref "R133") (pin "1") (pinfunction "1_1") (pintype "passive"))
      (node (ref "U25") (pin "1") (pinfunction "~{RST}_1") (pintype "input"))
    )
    (net (code "43") (name "P3V3") (class "Default")
      (node (ref "C141") (pin "2") (pinfunction "2_2") (pintype "passive"))
      (node (ref "C142") (pin "1") (pinfunction "1_1") (pintype "passive"))
      (node (ref "C172") (pin "2") (pinfunction "2_2") (pintype "passive"))
      (node (ref "C173") (pin "2") (pinfunction "2_2") (pintype "passive"))
      (node (ref "C174") (pin "2") (pinfunction "2_2") (pintype "passive"))
      (node (ref "C175") (pin "1") (pinfunction "1_1") (pintype "passive"))
      (node (ref "C176") (pin "1") (pinfunction "1_1") (pintype "passive"))
      (node (ref "C191") (pin "2") (pinfunction "2_2") (pintype "passive"))
      (node (ref "C192") (pin "2") (pinfunction "2_2") (pintype "passive"))
      (node (ref "C193") (pin "1") (pinfunction "1_1") (pintype "passive"))
      (node (ref "C194") (pin "1") (pinfunction "1_1") (pintype "passive"))
      (node (ref "C195") (pin "2") (pinfunction "2_2") (pintype "passive"))
      (node (ref "C196") (pin "2") (pinfunction "2_2") (pintype "passive"))
      (node (ref "C197") (pin "2") (pinfunction "2_2") (pintype "passive"))
      (node (ref "C198") (pin "1") (pinfunction "1_1") (pintype "passive"))
      (node (ref "C199") (pin "1") (pinfunction "1_1") (pintype "passive"))
      (node (ref "C200") (pin "2") (pinfunction "2_2") (pintype "passive"))
      (node (ref "C201") (pin "2") (pinfunction "2_2") (pintype "passive"))
      (node (ref "C202") (pin "1") (pinfunction "1_1") (pintype "passive"))
      (node (ref "C208") (pin "1") (pinfunction "1_1") (pintype "passive"))
      (node (ref "FB6") (pin "1") (pinfunction "1_1") (pintype "passive"))
      (node (ref "R119") (pin "2") (pinfunction "2_2") (pintype "passive"))
      (node (ref "R121") (pin "1") (pinfunction "1_1") (pintype "passive"))
      (node (ref "R122") (pin "1") (pinfunction "1_1") (pintype "passive"))
      (node (ref "R124") (pin "1") (pinfunction "1_1") (pintype "passive"))
      (node (ref "R127") (pin "2") (pinfunction "2_2") (pintype "passive"))
      (node (ref "R128") (pin "1") (pinfunction "1_1") (pintype "passive"))
      (node (ref "R129") (pin "2") (pinfunction "2_2") (pintype "passive"))
      (node (ref "R130") (pin "1") (pinfunction "1_1") (pintype "passive"))
      (node (ref "R131") (pin "2") (pinfunction "2_2") (pintype "passive"))
      (node (ref "R132") (pin "2") (pinfunction "2_2") (pintype "passive"))
      (node (ref "R133") (pin "2") (pinfunction "2_2") (pintype "passive"))
      (node (ref "R134") (pin "1") (pinfunction "1_1") (pintype "passive"))
      (node (ref "U19") (pin "15") (pinfunction "VDD33_15") (pintype "power_in"))
      (node (ref "U19") (pin "23") (pinfunction "VDD33_23") (pintype "power_in"))
      (node (ref "U19") (pin "27") (pinfunction "VBUS_DET_27") (pintype "power_in"))
      (node (ref "U19") (pin "36") (pinfunction "VDD33_36") (pintype "power_in"))
      (node (ref "U23") (pin "14") (pinfunction "VUSB_14") (pintype "power_in"))
      (node (ref "U23") (pin "18") (pinfunction "VDD_18") (pintype "power_in"))
      (node (ref "U24") (pin "10") (pinfunction "VUSB_10") (pintype "power_in"))
      (node (ref "U24") (pin "16") (pinfunction "VDD_16") (pintype "power_in"))
      (node (ref "U25") (pin "14") (pinfunction "VUSB_14") (pintype "power_in"))
      (node (ref "U25") (pin "18") (pinfunction "VDD_18") (pintype "power_in"))
    )
    (net (code "44") (name "RADIO_SPI_D_N") (class "Default")
      (node (ref "U19") (pin "8") (pinfunction "USBDM_DN4/PRT_DIS_M4_8") (pintype "bidirectional"))
      (node (ref "U25") (pin "15") (pinfunction "D-_15") (pintype "bidirectional"))
    )
    (net (code "45") (name "RADIO_SPI_D_P") (class "Default")
      (node (ref "U19") (pin "9") (pinfunction "USBDP_DN4/PRT_DIS_P4_9") (pintype "bidirectional"))
      (node (ref "U25") (pin "16") (pinfunction "D+_16") (pintype "bidirectional"))
    )
    (net (code "46") (name "RADIO_SPI_MISO") (class "Default")
      (node (ref "U25") (pin "10") (pinfunction "MISO_10") (pintype "input"))
    )
    (net (code "47") (name "RADIO_SPI_MOSI") (class "Default")
      (node (ref "U25") (pin "6") (pinfunction "MOSI_6") (pintype "output"))
    )
    (net (code "48") (name "RADIO_SPI_SCK") (class "Default")
      (node (ref "U25") (pin "8") (pinfunction "SCK_8") (pintype "output"))
    )
    (net (code "49") (name "SX1276_HFLF_CTRL") (class "Default")
      (node (ref "U25") (pin "7") (pinfunction "GP4_7") (pintype "bidirectional"))
    )
    (net (code "50") (name "SX1276_HF_TXRX_CTRL") (class "Default")
      (node (ref "U25") (pin "5") (pinfunction "GP3_5") (pintype "bidirectional"))
    )
    (net (code "51") (name "SX1276_LF_TXRX_CTRL") (class "Default")
      (node (ref "U25") (pin "4") (pinfunction "GP2_4") (pintype "bidirectional"))
    )
    (net (code "52") (name "UART_I2C_D_N") (class "Default")
      (node (ref "U19") (pin "6") (pinfunction "USBDM_DN3/PRT_DOS_M3_6") (pintype "bidirectional"))
      (node (ref "U24") (pin "11") (pinfunction "D-_11") (pintype "passive"))
    )
    (net (code "53") (name "UART_I2C_D_P") (class "Default")
      (node (ref "U19") (pin "7") (pinfunction "USBDP_DN3/PRT_DIS_P3_7") (pintype "bidirectional"))
      (node (ref "U24") (pin "12") (pinfunction "D+_12") (pintype "passive"))
    )
    (net (code "54") (name "USB2_D_N") (class "Default")
      (node (ref "U19") (pin "30") (pinfunction "USBDM_UP_30") (pintype "bidirectional"))
    )
    (net (code "55") (name "USB2_D_P") (class "Default")
      (node (ref "U19") (pin "31") (pinfunction "USBDP_UP_31") (pintype "bidirectional"))
    )
    (net (code "56") (name "USB_DPLL_RST") (class "Default")
      (node (ref "U24") (pin "6") (pinfunction "GP2_6") (pintype "bidirectional"))
    )
    (net (code "57") (name "USB_I2C_SCL") (class "Default")
      (node (ref "R131") (pin "1") (pinfunction "1_1") (pintype "passive"))
      (node (ref "U24") (pin "9") (pinfunction "SCL_9") (pintype "bidirectional"))
    )
    (net (code "58") (name "USB_I2C_SDA") (class "Default")
      (node (ref "R132") (pin "1") (pinfunction "1_1") (pintype "passive"))
      (node (ref "U24") (pin "8") (pinfunction "SDA_8") (pintype "bidirectional"))
    )
    (net (code "59") (name "USB_UART_RX") (class "Default")
      (node (ref "U24") (pin "4") (pinfunction "URx_4") (pintype "input"))
    )
    (net (code "60") (name "USB_UART_TX") (class "Default")
      (node (ref "U24") (pin "5") (pinfunction "UTx_5") (pintype "output"))
    )
    (net (code "61") (name "unconnected-(U19-PRTPWR1{slash}BC_EN1-Pad12)") (class "Default")
      (node (ref "U19") (pin "12") (pinfunction "PRTPWR1/BC_EN1_12") (pintype "bidirectional"))
    )
    (net (code "62") (name "unconnected-(U19-PRTPWR2{slash}BC_EN2-Pad16)") (class "Default")
      (node (ref "U19") (pin "16") (pinfunction "PRTPWR2/BC_EN2_16") (pintype "bidirectional"))
    )
    (net (code "63") (name "unconnected-(U19-PRTPWR3{slash}BC_EN3-Pad18)") (class "Default")
      (node (ref "U19") (pin "18") (pinfunction "PRTPWR3/BC_EN3_18") (pintype "bidirectional"))
    )
    (net (code "64") (name "unconnected-(U19-PRTPWR4{slash}BC_EN4-Pad20)") (class "Default")
      (node (ref "U19") (pin "20") (pinfunction "PRTPWR4/BC_EN4_20") (pintype "bidirectional"))
    )
    (net (code "65") (name "unconnected-(U19-TEST-Pad11)") (class "Default")
      (node (ref "U19") (pin "11") (pinfunction "TEST_11") (pintype "input"))
    )
    (net (code "66") (name "unconnected-(U23-GP5-Pad9)") (class "Default")
      (node (ref "U23") (pin "9") (pinfunction "GP5_9") (pintype "bidirectional"))
    )
    (net (code "67") (name "unconnected-(U23-GP6-Pad11)") (class "Default")
      (node (ref "U23") (pin "11") (pinfunction "GP6_11") (pintype "bidirectional"))
    )
    (net (code "68") (name "unconnected-(U23-GP7-Pad12)") (class "Default")
      (node (ref "U23") (pin "12") (pinfunction "GP7_12") (pintype "bidirectional"))
    )
    (net (code "69") (name "unconnected-(U24-NC-Pad14)") (class "Default")
      (node (ref "U24") (pin "14") (pinfunction "NC_14") (pintype "passive"))
    )
    (net (code "70") (name "unconnected-(U24-NC-Pad15)") (class "Default")
      (node (ref "U24") (pin "15") (pinfunction "NC_15") (pintype "passive"))
    )
    (net (code "71") (name "unconnected-(U25-GP5-Pad9)") (class "Default")
      (node (ref "U25") (pin "9") (pinfunction "GP5_9") (pintype "bidirectional"))
    )
    (net (code "72") (name "unconnected-(U25-GP6-Pad11)") (class "Default")
      (node (ref "U25") (pin "11") (pinfunction "GP6_11") (pintype "bidirectional"))
    )
    (net (code "73") (name "unconnected-(U25-GP7-Pad12)") (class "Default")
      (node (ref "U25") (pin "12") (pinfunction "GP7_12") (pintype "bidirectional"))
    )
  )
)
